# anemo4.net
KiCad netlist of a schematic drawn in EAGLE
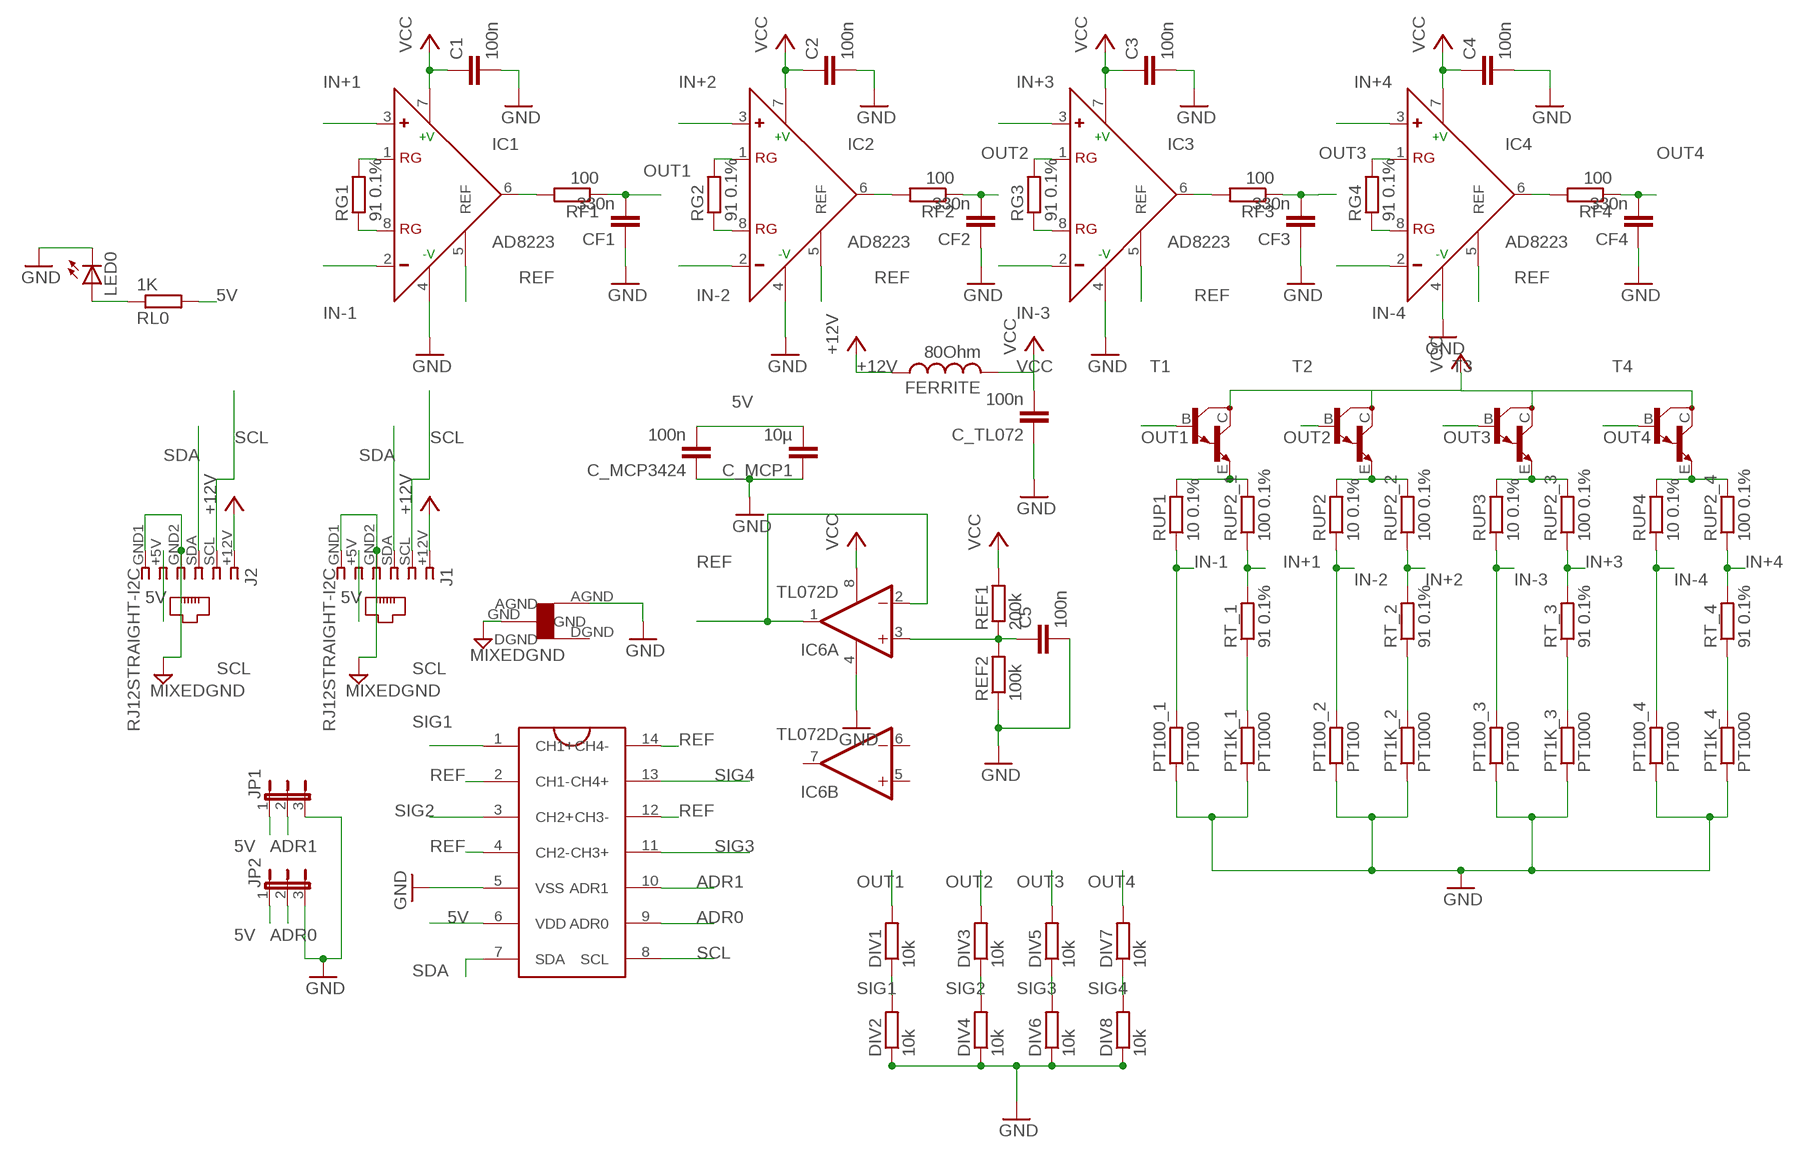
[diagram p0: schematic, sheet 1]

(export (version "E")
  (design (tool "Eeschema 10.0.6"))
  (components
    (comp (ref "C1")
      (value "100n")
      (footprint "eagle-import:C1206")
      (libsource (lib "eagle-import") (part "C-EUC1206"))
    )
    (comp (ref "C2")
      (value "100n")
      (footprint "eagle-import:C1206")
      (libsource (lib "eagle-import") (part "C-EUC1206"))
    )
    (comp (ref "C3")
      (value "100n")
      (footprint "eagle-import:C1206")
      (libsource (lib "eagle-import") (part "C-EUC1206"))
    )
    (comp (ref "C4")
      (value "100n")
      (footprint "eagle-import:C1206")
      (libsource (lib "eagle-import") (part "C-EUC1206"))
    )
    (comp (ref "C5")
      (value "100n")
      (footprint "eagle-import:C1206")
      (libsource (lib "eagle-import") (part "C-EUC1206"))
    )
    (comp (ref "CF1")
      (value "330n")
      (footprint "eagle-import:C1206")
      (libsource (lib "eagle-import") (part "C-EUC1206"))
    )
    (comp (ref "CF2")
      (value "330n")
      (footprint "eagle-import:C1206")
      (libsource (lib "eagle-import") (part "C-EUC1206"))
    )
    (comp (ref "CF3")
      (value "330n")
      (footprint "eagle-import:C1206")
      (libsource (lib "eagle-import") (part "C-EUC1206"))
    )
    (comp (ref "CF4")
      (value "330n")
      (footprint "eagle-import:C1206")
      (libsource (lib "eagle-import") (part "C-EUC1206"))
    )
    (comp (ref "C_MCP1")
      (value "10µ")
      (footprint "eagle-import:C1206")
      (libsource (lib "eagle-import") (part "C-EUC1206"))
    )
    (comp (ref "C_MCP3424")
      (value "100n")
      (footprint "eagle-import:C1206")
      (libsource (lib "eagle-import") (part "C-EUC1206"))
    )
    (comp (ref "C_TL072")
      (value "100n")
      (footprint "eagle-import:C1206")
      (libsource (lib "eagle-import") (part "C-EUC1206"))
    )
    (comp (ref "DIV1")
      (value "10k")
      (footprint "eagle-import:M1206")
      (libsource (lib "eagle-import") (part "R-EU_M1206"))
    )
    (comp (ref "DIV2")
      (value "10k")
      (footprint "eagle-import:M1206")
      (libsource (lib "eagle-import") (part "R-EU_M1206"))
    )
    (comp (ref "DIV3")
      (value "10k")
      (footprint "eagle-import:M1206")
      (libsource (lib "eagle-import") (part "R-EU_M1206"))
    )
    (comp (ref "DIV4")
      (value "10k")
      (footprint "eagle-import:M1206")
      (libsource (lib "eagle-import") (part "R-EU_M1206"))
    )
    (comp (ref "DIV5")
      (value "10k")
      (footprint "eagle-import:M1206")
      (libsource (lib "eagle-import") (part "R-EU_M1206"))
    )
    (comp (ref "DIV6")
      (value "10k")
      (footprint "eagle-import:M1206")
      (libsource (lib "eagle-import") (part "R-EU_M1206"))
    )
    (comp (ref "DIV7")
      (value "10k")
      (footprint "eagle-import:M1206")
      (libsource (lib "eagle-import") (part "R-EU_M1206"))
    )
    (comp (ref "DIV8")
      (value "10k")
      (footprint "eagle-import:M1206")
      (libsource (lib "eagle-import") (part "R-EU_M1206"))
    )
    (comp (ref "FERRITE")
      (value "80Ohm")
      (footprint "eagle-import:L3216C")
      (libsource (lib "eagle-import") (part "L-USL3216C"))
    )
    (comp (ref "IC1")
      (value "AD8223")
      (footprint "eagle-import:SO8")
      (fields (field (name "MPN") "AD620AR"))
      (libsource (lib "eagle-import") (part "AD620R"))
    )
    (comp (ref "IC2")
      (value "AD8223")
      (footprint "eagle-import:SO8")
      (fields (field (name "MPN") "AD620AR"))
      (libsource (lib "eagle-import") (part "AD620R"))
    )
    (comp (ref "IC3")
      (value "AD8223")
      (footprint "eagle-import:SO8")
      (fields (field (name "MPN") "AD620AR"))
      (libsource (lib "eagle-import") (part "AD620R"))
    )
    (comp (ref "IC4")
      (value "AD8223")
      (footprint "eagle-import:SO8")
      (fields (field (name "MPN") "AD620AR"))
      (libsource (lib "eagle-import") (part "AD620R"))
    )
    (comp (ref "IC6")
      (value "TL072D")
      (footprint "eagle-import:SO08")
      (libsource (lib "eagle-import") (part "TL072D"))
    )
    (comp (ref "J1")
      (value "RJ12STRAIGHT-I2C")
      (footprint "eagle-import:RJ12-STRAIGHT-I2C")
      (libsource (lib "eagle-import") (part "RJ12STRAIGHT-I2C"))
    )
    (comp (ref "J2")
      (value "RJ12STRAIGHT-I2C")
      (footprint "eagle-import:RJ12-STRAIGHT-I2C")
      (libsource (lib "eagle-import") (part "RJ12STRAIGHT-I2C"))
    )
    (comp (ref "JP1")
      (value "JP2E")
      (footprint "eagle-import:JP2")
      (libsource (lib "eagle-import") (part "JP2E"))
    )
    (comp (ref "JP2")
      (value "JP2E")
      (footprint "eagle-import:JP2")
      (libsource (lib "eagle-import") (part "JP2E"))
    )
    (comp (ref "LED0")
      (value "LED1206")
      (footprint "eagle-import:LED-1206")
      (libsource (lib "eagle-import") (part "LED1206"))
    )
    (comp (ref "PT1K_1")
      (value "PT1000")
      (footprint "eagle-import:M1206")
      (libsource (lib "eagle-import") (part "R-EU_M1206"))
    )
    (comp (ref "PT1K_2")
      (value "PT1000")
      (footprint "eagle-import:M1206")
      (libsource (lib "eagle-import") (part "R-EU_M1206"))
    )
    (comp (ref "PT1K_3")
      (value "PT1000")
      (footprint "eagle-import:M1206")
      (libsource (lib "eagle-import") (part "R-EU_M1206"))
    )
    (comp (ref "PT1K_4")
      (value "PT1000")
      (footprint "eagle-import:M1206")
      (libsource (lib "eagle-import") (part "R-EU_M1206"))
    )
    (comp (ref "PT100_1")
      (value "PT100")
      (footprint "eagle-import:M1206")
      (libsource (lib "eagle-import") (part "R-EU_M1206"))
    )
    (comp (ref "PT100_2")
      (value "PT100")
      (footprint "eagle-import:M1206")
      (libsource (lib "eagle-import") (part "R-EU_M1206"))
    )
    (comp (ref "PT100_3")
      (value "PT100")
      (footprint "eagle-import:M1206")
      (libsource (lib "eagle-import") (part "R-EU_M1206"))
    )
    (comp (ref "PT100_4")
      (value "PT100")
      (footprint "eagle-import:M1206")
      (libsource (lib "eagle-import") (part "R-EU_M1206"))
    )
    (comp (ref "REF1")
      (value "200k")
      (footprint "eagle-import:M1206")
      (libsource (lib "eagle-import") (part "R-EU_M1206"))
    )
    (comp (ref "REF2")
      (value "100k")
      (footprint "eagle-import:M1206")
      (libsource (lib "eagle-import") (part "R-EU_M1206"))
    )
    (comp (ref "RF1")
      (value "100")
      (footprint "eagle-import:M1206")
      (libsource (lib "eagle-import") (part "R-EU_M1206"))
    )
    (comp (ref "RF2")
      (value "100")
      (footprint "eagle-import:M1206")
      (libsource (lib "eagle-import") (part "R-EU_M1206"))
    )
    (comp (ref "RF3")
      (value "100")
      (footprint "eagle-import:M1206")
      (libsource (lib "eagle-import") (part "R-EU_M1206"))
    )
    (comp (ref "RF4")
      (value "100")
      (footprint "eagle-import:M1206")
      (libsource (lib "eagle-import") (part "R-EU_M1206"))
    )
    (comp (ref "RG1")
      (value "91 0.1%")
      (footprint "eagle-import:M1206")
      (libsource (lib "eagle-import") (part "R-EU_M1206"))
    )
    (comp (ref "RG2")
      (value "91 0.1%")
      (footprint "eagle-import:M1206")
      (libsource (lib "eagle-import") (part "R-EU_M1206"))
    )
    (comp (ref "RG3")
      (value "91 0.1%")
      (footprint "eagle-import:M1206")
      (libsource (lib "eagle-import") (part "R-EU_M1206"))
    )
    (comp (ref "RG4")
      (value "91 0.1%")
      (footprint "eagle-import:M1206")
      (libsource (lib "eagle-import") (part "R-EU_M1206"))
    )
    (comp (ref "RL0")
      (value "1K")
      (footprint "eagle-import:M1206")
      (libsource (lib "eagle-import") (part "R-EU_M1206"))
    )
    (comp (ref "RT_1")
      (value "91 0.1%")
      (footprint "eagle-import:M1206")
      (libsource (lib "eagle-import") (part "R-EU_M1206"))
    )
    (comp (ref "RT_2")
      (value "91 0.1%")
      (footprint "eagle-import:M1206")
      (libsource (lib "eagle-import") (part "R-EU_M1206"))
    )
    (comp (ref "RT_3")
      (value "91 0.1%")
      (footprint "eagle-import:M1206")
      (libsource (lib "eagle-import") (part "R-EU_M1206"))
    )
    (comp (ref "RT_4")
      (value "91 0.1%")
      (footprint "eagle-import:M1206")
      (libsource (lib "eagle-import") (part "R-EU_M1206"))
    )
    (comp (ref "RUP1")
      (value "10 0.1%")
      (footprint "eagle-import:M1206")
      (libsource (lib "eagle-import") (part "R-EU_M1206"))
    )
    (comp (ref "RUP2")
      (value "10 0.1%")
      (footprint "eagle-import:M1206")
      (libsource (lib "eagle-import") (part "R-EU_M1206"))
    )
    (comp (ref "RUP2_1")
      (value "100 0.1%")
      (footprint "eagle-import:M1206")
      (libsource (lib "eagle-import") (part "R-EU_M1206"))
    )
    (comp (ref "RUP2_2")
      (value "100 0.1%")
      (footprint "eagle-import:M1206")
      (libsource (lib "eagle-import") (part "R-EU_M1206"))
    )
    (comp (ref "RUP2_3")
      (value "100 0.1%")
      (footprint "eagle-import:M1206")
      (libsource (lib "eagle-import") (part "R-EU_M1206"))
    )
    (comp (ref "RUP2_4")
      (value "100 0.1%")
      (footprint "eagle-import:M1206")
      (libsource (lib "eagle-import") (part "R-EU_M1206"))
    )
    (comp (ref "RUP3")
      (value "10 0.1%")
      (footprint "eagle-import:M1206")
      (libsource (lib "eagle-import") (part "R-EU_M1206"))
    )
    (comp (ref "RUP4")
      (value "10 0.1%")
      (footprint "eagle-import:M1206")
      (libsource (lib "eagle-import") (part "R-EU_M1206"))
    )
    (comp (ref "T1")
      (value "MMBTA13LT1-NPN_DARL-SOT23-BEC")
      (footprint "eagle-import:SOT23-BEC")
      (libsource (lib "eagle-import") (part "-NPN_DARL-SOT23-BECMMBTA13LT1"))
    )
    (comp (ref "T2")
      (value "MMBTA13LT1-NPN_DARL-SOT23-BEC")
      (footprint "eagle-import:SOT23-BEC")
      (libsource (lib "eagle-import") (part "-NPN_DARL-SOT23-BECMMBTA13LT1"))
    )
    (comp (ref "T3")
      (value "MMBTA13LT1-NPN_DARL-SOT23-BEC")
      (footprint "eagle-import:SOT23-BEC")
      (libsource (lib "eagle-import") (part "-NPN_DARL-SOT23-BECMMBTA13LT1"))
    )
    (comp (ref "T4")
      (value "MMBTA13LT1-NPN_DARL-SOT23-BEC")
      (footprint "eagle-import:SOT23-BEC")
      (libsource (lib "eagle-import") (part "-NPN_DARL-SOT23-BECMMBTA13LT1"))
    )
    (comp (ref "U$1")
      (value "MCP3424(SO14)")
      (footprint "eagle-import:14LDSOIC")
      (libsource (lib "eagle-import") (part "MCP3424(SO14)"))
    )
    (comp (ref "U$2")
      (value "STARGND")
      (footprint "eagle-import:STAR")
      (libsource (lib "eagle-import") (part "STARGND"))
    )
  )
  (nets
    (net (code "1") (name "+12V") (class "Default")
      (node (ref "FERRITE") (pin "1") (pinfunction "1_1") (pintype "passive"))
      (node (ref "J1") (pin "+12V") (pinfunction "1_+12V") (pintype "bidirectional"))
      (node (ref "J2") (pin "+12V") (pinfunction "1_+12V") (pintype "bidirectional"))
    )
    (net (code "2") (name "/5V") (class "Default")
      (node (ref "C_MCP1") (pin "2") (pinfunction "2_2") (pintype "passive"))
      (node (ref "C_MCP3424") (pin "2") (pinfunction "2_2") (pintype "passive"))
      (node (ref "J1") (pin "+5V") (pinfunction "5_+5V") (pintype "bidirectional"))
      (node (ref "J2") (pin "+5V") (pinfunction "5_+5V") (pintype "bidirectional"))
      (node (ref "JP1") (pin "1") (pinfunction "1_1") (pintype "passive"))
      (node (ref "JP2") (pin "1") (pinfunction "1_1") (pintype "passive"))
      (node (ref "RL0") (pin "2") (pinfunction "2_2") (pintype "passive"))
      (node (ref "U$1") (pin "6") (pinfunction "VDD_6") (pintype "bidirectional"))
    )
    (net (code "3") (name "/ADR0") (class "Default")
      (node (ref "JP2") (pin "2") (pinfunction "2_2") (pintype "passive"))
      (node (ref "U$1") (pin "9") (pinfunction "ADR0_9") (pintype "bidirectional"))
    )
    (net (code "4") (name "/ADR1") (class "Default")
      (node (ref "JP1") (pin "2") (pinfunction "2_2") (pintype "passive"))
      (node (ref "U$1") (pin "10") (pinfunction "ADR1_10") (pintype "bidirectional"))
    )
    (net (code "5") (name "/IN+1") (class "Default")
      (node (ref "IC1") (pin "3") (pinfunction "+_3") (pintype "input"))
      (node (ref "RT_1") (pin "2") (pinfunction "2_2") (pintype "passive"))
      (node (ref "RUP2_1") (pin "1") (pinfunction "1_1") (pintype "passive"))
    )
    (net (code "6") (name "/IN+2") (class "Default")
      (node (ref "IC2") (pin "3") (pinfunction "+_3") (pintype "input"))
      (node (ref "RT_2") (pin "2") (pinfunction "2_2") (pintype "passive"))
      (node (ref "RUP2_2") (pin "1") (pinfunction "1_1") (pintype "passive"))
    )
    (net (code "7") (name "/IN+3") (class "Default")
      (node (ref "IC3") (pin "3") (pinfunction "+_3") (pintype "input"))
      (node (ref "RT_3") (pin "2") (pinfunction "2_2") (pintype "passive"))
      (node (ref "RUP2_3") (pin "1") (pinfunction "1_1") (pintype "passive"))
    )
    (net (code "8") (name "/IN+4") (class "Default")
      (node (ref "IC4") (pin "3") (pinfunction "+_3") (pintype "input"))
      (node (ref "RT_4") (pin "2") (pinfunction "2_2") (pintype "passive"))
      (node (ref "RUP2_4") (pin "1") (pinfunction "1_1") (pintype "passive"))
    )
    (net (code "9") (name "/IN-1") (class "Default")
      (node (ref "IC1") (pin "2") (pinfunction "-_2") (pintype "input"))
      (node (ref "PT100_1") (pin "2") (pinfunction "2_2") (pintype "passive"))
      (node (ref "RUP1") (pin "1") (pinfunction "1_1") (pintype "passive"))
    )
    (net (code "10") (name "/IN-2") (class "Default")
      (node (ref "IC2") (pin "2") (pinfunction "-_2") (pintype "input"))
      (node (ref "PT100_2") (pin "2") (pinfunction "2_2") (pintype "passive"))
      (node (ref "RUP2") (pin "1") (pinfunction "1_1") (pintype "passive"))
    )
    (net (code "11") (name "/IN-3") (class "Default")
      (node (ref "IC3") (pin "2") (pinfunction "-_2") (pintype "input"))
      (node (ref "PT100_3") (pin "2") (pinfunction "2_2") (pintype "passive"))
      (node (ref "RUP3") (pin "1") (pinfunction "1_1") (pintype "passive"))
    )
    (net (code "12") (name "/IN-4") (class "Default")
      (node (ref "IC4") (pin "2") (pinfunction "-_2") (pintype "input"))
      (node (ref "PT100_4") (pin "2") (pinfunction "2_2") (pintype "passive"))
      (node (ref "RUP4") (pin "1") (pinfunction "1_1") (pintype "passive"))
    )
    (net (code "13") (name "/OUT1") (class "Default")
      (node (ref "CF1") (pin "2") (pinfunction "2_2") (pintype "passive"))
      (node (ref "DIV1") (pin "2") (pinfunction "2_2") (pintype "passive"))
      (node (ref "RF1") (pin "1") (pinfunction "1_1") (pintype "passive"))
      (node (ref "T1") (pin "B") (pinfunction "B_B") (pintype "passive"))
    )
    (net (code "14") (name "/OUT2") (class "Default")
      (node (ref "CF2") (pin "2") (pinfunction "2_2") (pintype "passive"))
      (node (ref "DIV3") (pin "2") (pinfunction "2_2") (pintype "passive"))
      (node (ref "RF2") (pin "1") (pinfunction "1_1") (pintype "passive"))
      (node (ref "T2") (pin "B") (pinfunction "B_B") (pintype "passive"))
    )
    (net (code "15") (name "/OUT3") (class "Default")
      (node (ref "CF3") (pin "2") (pinfunction "2_2") (pintype "passive"))
      (node (ref "DIV5") (pin "2") (pinfunction "2_2") (pintype "passive"))
      (node (ref "RF3") (pin "1") (pinfunction "1_1") (pintype "passive"))
      (node (ref "T3") (pin "B") (pinfunction "B_B") (pintype "passive"))
    )
    (net (code "16") (name "/OUT4") (class "Default")
      (node (ref "CF4") (pin "2") (pinfunction "2_2") (pintype "passive"))
      (node (ref "DIV7") (pin "2") (pinfunction "2_2") (pintype "passive"))
      (node (ref "RF4") (pin "1") (pinfunction "1_1") (pintype "passive"))
      (node (ref "T4") (pin "B") (pinfunction "B_B") (pintype "passive"))
    )
    (net (code "17") (name "/REF") (class "Default")
      (node (ref "IC1") (pin "5") (pinfunction "REF_5") (pintype "passive"))
      (node (ref "IC2") (pin "5") (pinfunction "REF_5") (pintype "passive"))
      (node (ref "IC3") (pin "5") (pinfunction "REF_5") (pintype "passive"))
      (node (ref "IC4") (pin "5") (pinfunction "REF_5") (pintype "passive"))
      (node (ref "IC6") (pin "1") (pinfunction "OUT_1") (pintype "output"))
      (node (ref "IC6") (pin "2") (pinfunction "-IN_2") (pintype "input"))
      (node (ref "U$1") (pin "12") (pinfunction "CH3-_12") (pintype "bidirectional"))
      (node (ref "U$1") (pin "14") (pinfunction "CH4-_14") (pintype "bidirectional"))
      (node (ref "U$1") (pin "2") (pinfunction "CH1-_2") (pintype "bidirectional"))
      (node (ref "U$1") (pin "4") (pinfunction "CH2-_4") (pintype "bidirectional"))
    )
    (net (code "18") (name "/SCL") (class "Default")
      (node (ref "J1") (pin "SCL") (pinfunction "2_SCL") (pintype "bidirectional"))
      (node (ref "J2") (pin "SCL") (pinfunction "2_SCL") (pintype "bidirectional"))
      (node (ref "U$1") (pin "8") (pinfunction "SCL_8") (pintype "bidirectional"))
    )
    (net (code "19") (name "/SDA") (class "Default")
      (node (ref "J1") (pin "SDA") (pinfunction "3_SDA") (pintype "bidirectional"))
      (node (ref "J2") (pin "SDA") (pinfunction "3_SDA") (pintype "bidirectional"))
      (node (ref "U$1") (pin "7") (pinfunction "SDA_7") (pintype "bidirectional"))
    )
    (net (code "20") (name "/SIG1") (class "Default")
      (node (ref "DIV1") (pin "1") (pinfunction "1_1") (pintype "passive"))
      (node (ref "DIV2") (pin "2") (pinfunction "2_2") (pintype "passive"))
      (node (ref "U$1") (pin "1") (pinfunction "CH1+_1") (pintype "bidirectional"))
    )
    (net (code "21") (name "/SIG2") (class "Default")
      (node (ref "DIV3") (pin "1") (pinfunction "1_1") (pintype "passive"))
      (node (ref "DIV4") (pin "2") (pinfunction "2_2") (pintype "passive"))
      (node (ref "U$1") (pin "3") (pinfunction "CH2+_3") (pintype "bidirectional"))
    )
    (net (code "22") (name "/SIG3") (class "Default")
      (node (ref "DIV5") (pin "1") (pinfunction "1_1") (pintype "passive"))
      (node (ref "DIV6") (pin "2") (pinfunction "2_2") (pintype "passive"))
      (node (ref "U$1") (pin "11") (pinfunction "CH3+_11") (pintype "bidirectional"))
    )
    (net (code "23") (name "/SIG4") (class "Default")
      (node (ref "DIV7") (pin "1") (pinfunction "1_1") (pintype "passive"))
      (node (ref "DIV8") (pin "2") (pinfunction "2_2") (pintype "passive"))
      (node (ref "U$1") (pin "13") (pinfunction "CH4+_13") (pintype "bidirectional"))
    )
    (net (code "24") (name "GND") (class "Default")
      (node (ref "C1") (pin "2") (pinfunction "2_2") (pintype "passive"))
      (node (ref "C2") (pin "2") (pinfunction "2_2") (pintype "passive"))
      (node (ref "C3") (pin "2") (pinfunction "2_2") (pintype "passive"))
      (node (ref "C4") (pin "2") (pinfunction "2_2") (pintype "passive"))
      (node (ref "C5") (pin "2") (pinfunction "2_2") (pintype "passive"))
      (node (ref "CF1") (pin "1") (pinfunction "1_1") (pintype "passive"))
      (node (ref "CF2") (pin "1") (pinfunction "1_1") (pintype "passive"))
      (node (ref "CF3") (pin "1") (pinfunction "1_1") (pintype "passive"))
      (node (ref "CF4") (pin "1") (pinfunction "1_1") (pintype "passive"))
      (node (ref "C_MCP1") (pin "1") (pinfunction "1_1") (pintype "passive"))
      (node (ref "C_MCP3424") (pin "1") (pinfunction "1_1") (pintype "passive"))
      (node (ref "C_TL072") (pin "1") (pinfunction "1_1") (pintype "passive"))
      (node (ref "DIV2") (pin "1") (pinfunction "1_1") (pintype "passive"))
      (node (ref "DIV4") (pin "1") (pinfunction "1_1") (pintype "passive"))
      (node (ref "DIV6") (pin "1") (pinfunction "1_1") (pintype "passive"))
      (node (ref "DIV8") (pin "1") (pinfunction "1_1") (pintype "passive"))
      (node (ref "IC1") (pin "4") (pinfunction "-V_4") (pintype "power_in"))
      (node (ref "IC2") (pin "4") (pinfunction "-V_4") (pintype "power_in"))
      (node (ref "IC3") (pin "4") (pinfunction "-V_4") (pintype "power_in"))
      (node (ref "IC4") (pin "4") (pinfunction "-V_4") (pintype "power_in"))
      (node (ref "IC6") (pin "4") (pinfunction "V-_4") (pintype "power_in"))
      (node (ref "JP1") (pin "3") (pinfunction "3_3") (pintype "passive"))
      (node (ref "JP2") (pin "3") (pinfunction "3_3") (pintype "passive"))
      (node (ref "LED0") (pin "C") (pinfunction "C_C") (pintype "passive"))
      (node (ref "PT100_1") (pin "1") (pinfunction "1_1") (pintype "passive"))
      (node (ref "PT100_2") (pin "1") (pinfunction "1_1") (pintype "passive"))
      (node (ref "PT100_3") (pin "1") (pinfunction "1_1") (pintype "passive"))
      (node (ref "PT100_4") (pin "1") (pinfunction "1_1") (pintype "passive"))
      (node (ref "PT1K_1") (pin "1") (pinfunction "1_1") (pintype "passive"))
      (node (ref "PT1K_2") (pin "1") (pinfunction "1_1") (pintype "passive"))
      (node (ref "PT1K_3") (pin "1") (pinfunction "1_1") (pintype "passive"))
      (node (ref "PT1K_4") (pin "1") (pinfunction "1_1") (pintype "passive"))
      (node (ref "REF2") (pin "1") (pinfunction "1_1") (pintype "passive"))
      (node (ref "U$1") (pin "5") (pinfunction "VSS_5") (pintype "bidirectional"))
      (node (ref "U$2") (pin "AGND") (pinfunction "AGND_AGND") (pintype "output"))
    )
    (net (code "25") (name "MIXEDGND") (class "Default")
      (node (ref "J1") (pin "GND1") (pinfunction "6_GND1") (pintype "bidirectional"))
      (node (ref "J1") (pin "GND2") (pinfunction "4_GND2") (pintype "bidirectional"))
      (node (ref "J2") (pin "GND1") (pinfunction "6_GND1") (pintype "bidirectional"))
      (node (ref "J2") (pin "GND2") (pinfunction "4_GND2") (pintype "bidirectional"))
      (node (ref "U$2") (pin "GND") (pinfunction "GND_GND") (pintype "power_in"))
    )
    (net (code "26") (name "Net-(IC1-OUT)") (class "Default")
      (node (ref "IC1") (pin "6") (pinfunction "OUT_6") (pintype "output"))
      (node (ref "RF1") (pin "2") (pinfunction "2_2") (pintype "passive"))
    )
    (net (code "27") (name "Net-(IC1-RG-Pad1)") (class "Default")
      (node (ref "IC1") (pin "1") (pinfunction "RG_1") (pintype "passive"))
      (node (ref "RG1") (pin "2") (pinfunction "2_2") (pintype "passive"))
    )
    (net (code "28") (name "Net-(IC1-RG-Pad8)") (class "Default")
      (node (ref "IC1") (pin "8") (pinfunction "RG_8") (pintype "passive"))
      (node (ref "RG1") (pin "1") (pinfunction "1_1") (pintype "passive"))
    )
    (net (code "29") (name "Net-(IC2-OUT)") (class "Default")
      (node (ref "IC2") (pin "6") (pinfunction "OUT_6") (pintype "output"))
      (node (ref "RF2") (pin "2") (pinfunction "2_2") (pintype "passive"))
    )
    (net (code "30") (name "Net-(IC2-RG-Pad1)") (class "Default")
      (node (ref "IC2") (pin "1") (pinfunction "RG_1") (pintype "passive"))
      (node (ref "RG2") (pin "2") (pinfunction "2_2") (pintype "passive"))
    )
    (net (code "31") (name "Net-(IC2-RG-Pad8)") (class "Default")
      (node (ref "IC2") (pin "8") (pinfunction "RG_8") (pintype "passive"))
      (node (ref "RG2") (pin "1") (pinfunction "1_1") (pintype "passive"))
    )
    (net (code "32") (name "Net-(IC3-OUT)") (class "Default")
      (node (ref "IC3") (pin "6") (pinfunction "OUT_6") (pintype "output"))
      (node (ref "RF3") (pin "2") (pinfunction "2_2") (pintype "passive"))
    )
    (net (code "33") (name "Net-(IC3-RG-Pad1)") (class "Default")
      (node (ref "IC3") (pin "1") (pinfunction "RG_1") (pintype "passive"))
      (node (ref "RG3") (pin "2") (pinfunction "2_2") (pintype "passive"))
    )
    (net (code "34") (name "Net-(IC3-RG-Pad8)") (class "Default")
      (node (ref "IC3") (pin "8") (pinfunction "RG_8") (pintype "passive"))
      (node (ref "RG3") (pin "1") (pinfunction "1_1") (pintype "passive"))
    )
    (net (code "35") (name "Net-(IC4-OUT)") (class "Default")
      (node (ref "IC4") (pin "6") (pinfunction "OUT_6") (pintype "output"))
      (node (ref "RF4") (pin "2") (pinfunction "2_2") (pintype "passive"))
    )
    (net (code "36") (name "Net-(IC4-RG-Pad1)") (class "Default")
      (node (ref "IC4") (pin "1") (pinfunction "RG_1") (pintype "passive"))
      (node (ref "RG4") (pin "2") (pinfunction "2_2") (pintype "passive"))
    )
    (net (code "37") (name "Net-(IC4-RG-Pad8)") (class "Default")
      (node (ref "IC4") (pin "8") (pinfunction "RG_8") (pintype "passive"))
      (node (ref "RG4") (pin "1") (pinfunction "1_1") (pintype "passive"))
    )
    (net (code "38") (name "Net-(IC6A-+IN)") (class "Default")
      (node (ref "C5") (pin "1") (pinfunction "1_1") (pintype "passive"))
      (node (ref "IC6") (pin "3") (pinfunction "+IN_3") (pintype "input"))
      (node (ref "REF1") (pin "1") (pinfunction "1_1") (pintype "passive"))
      (node (ref "REF2") (pin "2") (pinfunction "2_2") (pintype "passive"))
    )
    (net (code "39") (name "Net-(LED0-PadA)") (class "Default")
      (node (ref "LED0") (pin "A") (pinfunction "A_A") (pintype "passive"))
      (node (ref "RL0") (pin "1") (pinfunction "1_1") (pintype "passive"))
    )
    (net (code "40") (name "Net-(PT1K_1-Pad2)") (class "Default")
      (node (ref "PT1K_1") (pin "2") (pinfunction "2_2") (pintype "passive"))
      (node (ref "RT_1") (pin "1") (pinfunction "1_1") (pintype "passive"))
    )
    (net (code "41") (name "Net-(PT1K_2-Pad2)") (class "Default")
      (node (ref "PT1K_2") (pin "2") (pinfunction "2_2") (pintype "passive"))
      (node (ref "RT_2") (pin "1") (pinfunction "1_1") (pintype "passive"))
    )
    (net (code "42") (name "Net-(PT1K_3-Pad2)") (class "Default")
      (node (ref "PT1K_3") (pin "2") (pinfunction "2_2") (pintype "passive"))
      (node (ref "RT_3") (pin "1") (pinfunction "1_1") (pintype "passive"))
    )
    (net (code "43") (name "Net-(PT1K_4-Pad2)") (class "Default")
      (node (ref "PT1K_4") (pin "2") (pinfunction "2_2") (pintype "passive"))
      (node (ref "RT_4") (pin "1") (pinfunction "1_1") (pintype "passive"))
    )
    (net (code "44") (name "Net-(RUP1-Pad2)") (class "Default")
      (node (ref "RUP1") (pin "2") (pinfunction "2_2") (pintype "passive"))
      (node (ref "RUP2_1") (pin "2") (pinfunction "2_2") (pintype "passive"))
      (node (ref "T1") (pin "E") (pinfunction "E_E") (pintype "passive"))
    )
    (net (code "45") (name "Net-(RUP2-Pad2)") (class "Default")
      (node (ref "RUP2") (pin "2") (pinfunction "2_2") (pintype "passive"))
      (node (ref "RUP2_2") (pin "2") (pinfunction "2_2") (pintype "passive"))
      (node (ref "T2") (pin "E") (pinfunction "E_E") (pintype "passive"))
    )
    (net (code "46") (name "Net-(RUP2_3-Pad2)") (class "Default")
      (node (ref "RUP2_3") (pin "2") (pinfunction "2_2") (pintype "passive"))
      (node (ref "RUP3") (pin "2") (pinfunction "2_2") (pintype "passive"))
      (node (ref "T3") (pin "E") (pinfunction "E_E") (pintype "passive"))
    )
    (net (code "47") (name "Net-(RUP2_4-Pad2)") (class "Default")
      (node (ref "RUP2_4") (pin "2") (pinfunction "2_2") (pintype "passive"))
      (node (ref "RUP4") (pin "2") (pinfunction "2_2") (pintype "passive"))
      (node (ref "T4") (pin "E") (pinfunction "E_E") (pintype "passive"))
    )
    (net (code "48") (name "VCC") (class "Default")
      (node (ref "C1") (pin "1") (pinfunction "1_1") (pintype "passive"))
      (node (ref "C2") (pin "1") (pinfunction "1_1") (pintype "passive"))
      (node (ref "C3") (pin "1") (pinfunction "1_1") (pintype "passive"))
      (node (ref "C4") (pin "1") (pinfunction "1_1") (pintype "passive"))
      (node (ref "C_TL072") (pin "2") (pinfunction "2_2") (pintype "passive"))
      (node (ref "FERRITE") (pin "2") (pinfunction "2_2") (pintype "passive"))
      (node (ref "IC1") (pin "7") (pinfunction "+V_7") (pintype "power_in"))
      (node (ref "IC2") (pin "7") (pinfunction "+V_7") (pintype "power_in"))
      (node (ref "IC3") (pin "7") (pinfunction "+V_7") (pintype "power_in"))
      (node (ref "IC4") (pin "7") (pinfunction "+V_7") (pintype "power_in"))
      (node (ref "IC6") (pin "8") (pinfunction "V+_8") (pintype "power_in"))
      (node (ref "REF1") (pin "2") (pinfunction "2_2") (pintype "passive"))
      (node (ref "T1") (pin "C") (pinfunction "C_C") (pintype "passive"))
      (node (ref "T2") (pin "C") (pinfunction "C_C") (pintype "passive"))
      (node (ref "T3") (pin "C") (pinfunction "C_C") (pintype "passive"))
      (node (ref "T4") (pin "C") (pinfunction "C_C") (pintype "passive"))
    )
    (net (code "49") (name "unconnected-(IC6B-+IN-Pad5)") (class "Default")
      (node (ref "IC6") (pin "5") (pinfunction "+IN_5") (pintype "input"))
    )
    (net (code "50") (name "unconnected-(IC6B--IN-Pad6)") (class "Default")
      (node (ref "IC6") (pin "6") (pinfunction "-IN_6") (pintype "input"))
    )
    (net (code "51") (name "unconnected-(IC6B-OUT-Pad7)") (class "Default")
      (node (ref "IC6") (pin "7") (pinfunction "OUT_7") (pintype "output"))
    )
    (net (code "52") (name "unconnected-(U$2-PadDGND)") (class "Default")
      (node (ref "U$2") (pin "DGND") (pinfunction "DGND_DGND") (pintype "output"))
    )
  )
)
